# faros-328P-nrf8001-50x70.net
KiCad netlist of a schematic drawn in EAGLE
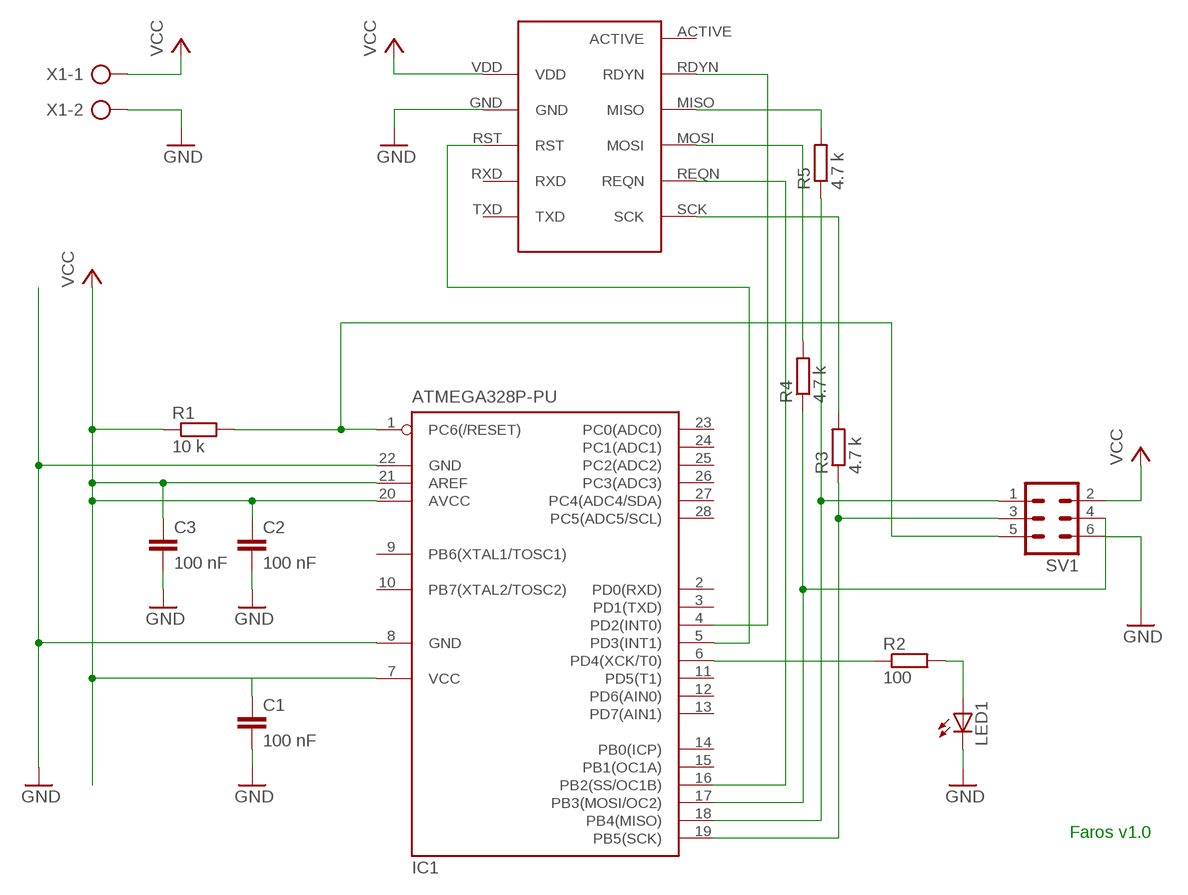
[diagram p0: schematic, sheet 1]

(export (version "E")
  (design (tool "Eeschema 10.0.6"))
  (components
    (comp (ref "C1")
      (value "100 nF")
      (footprint "eagle-import:C050-024X044")
      (libsource (lib "eagle-import") (part "C-EU050-024X044"))
    )
    (comp (ref "C2")
      (value "100 nF")
      (footprint "eagle-import:C050-024X044")
      (libsource (lib "eagle-import") (part "C-EU050-024X044"))
    )
    (comp (ref "C3")
      (value "100 nF")
      (footprint "eagle-import:C050-024X044")
      (libsource (lib "eagle-import") (part "C-EU050-024X044"))
    )
    (comp (ref "IC1")
      (value "ATMEGA328P-PU")
      (footprint "eagle-import:DIL28-3")
      (libsource (lib "eagle-import") (part "MEGA8-P"))
    )
    (comp (ref "LED1")
      (value "LED3MM")
      (footprint "eagle-import:LED3MM")
      (libsource (lib "eagle-import") (part "LED3MM"))
    )
    (comp (ref "MOD1")
      (value "MOD-NRF8001MOD-NRF8001")
      (footprint "eagle-import:MOD-NRF8001")
      (libsource (lib "eagle-import") (part "MOD-NRF8001MOD-NRF8001"))
    )
    (comp (ref "R1")
      (value "10 k")
      (footprint "eagle-import:0207_7")
      (libsource (lib "eagle-import") (part "R-EU_0207/7"))
    )
    (comp (ref "R2")
      (value "100")
      (footprint "eagle-import:0207_7")
      (libsource (lib "eagle-import") (part "R-EU_0207/7"))
    )
    (comp (ref "R3")
      (value "4.7 k")
      (footprint "eagle-import:0207_7")
      (libsource (lib "eagle-import") (part "R-EU_0207/7"))
    )
    (comp (ref "R4")
      (value "4.7 k")
      (footprint "eagle-import:0207_7")
      (libsource (lib "eagle-import") (part "R-EU_0207/7"))
    )
    (comp (ref "R5")
      (value "4.7 k")
      (footprint "eagle-import:0207_7")
      (libsource (lib "eagle-import") (part "R-EU_0207/7"))
    )
    (comp (ref "SV1")
      (value "MA03-2")
      (footprint "eagle-import:MA03-2")
      (libsource (lib "eagle-import") (part "MA03-2"))
    )
    (comp (ref "X1")
      (value "AK500/2")
      (footprint "eagle-import:AK500_2")
      (libsource (lib "eagle-import") (part "AK500/2"))
    )
  )
  (nets
    (net (code "1") (name "GND") (class "Default")
      (node (ref "C1") (pin "2") (pinfunction "2_2") (pintype "passive"))
      (node (ref "C2") (pin "2") (pinfunction "2_2") (pintype "passive"))
      (node (ref "C3") (pin "2") (pinfunction "2_2") (pintype "passive"))
      (node (ref "IC1") (pin "22") (pinfunction "GND_22") (pintype "power_in"))
      (node (ref "IC1") (pin "8") (pinfunction "GND_8") (pintype "power_in"))
      (node (ref "LED1") (pin "K") (pinfunction "C_K") (pintype "passive"))
      (node (ref "MOD1") (pin "GND") (pinfunction "GND_GND") (pintype "power_in"))
      (node (ref "SV1") (pin "6") (pinfunction "6_6") (pintype "passive"))
      (node (ref "X1") (pin "2") (pinfunction "KL_2") (pintype "passive"))
    )
    (net (code "2") (name "Net-(IC1-PB2(SS{slash}OC1B))") (class "Default")
      (node (ref "IC1") (pin "16") (pinfunction "PB2(SS/OC1B)_16") (pintype "bidirectional"))
      (node (ref "MOD1") (pin "REQN") (pinfunction "REQN_REQN") (pintype "input"))
    )
    (net (code "3") (name "Net-(IC1-PB3(MOSI{slash}OC2))") (class "Default")
      (node (ref "IC1") (pin "17") (pinfunction "PB3(MOSI/OC2)_17") (pintype "bidirectional"))
      (node (ref "R4") (pin "1") (pinfunction "1_1") (pintype "passive"))
      (node (ref "SV1") (pin "4") (pinfunction "4_4") (pintype "passive"))
    )
    (net (code "4") (name "Net-(IC1-PB4(MISO))") (class "Default")
      (node (ref "IC1") (pin "18") (pinfunction "PB4(MISO)_18") (pintype "bidirectional"))
      (node (ref "R5") (pin "1") (pinfunction "1_1") (pintype "passive"))
      (node (ref "SV1") (pin "1") (pinfunction "1_1") (pintype "passive"))
    )
    (net (code "5") (name "Net-(IC1-PB5(SCK))") (class "Default")
      (node (ref "IC1") (pin "19") (pinfunction "PB5(SCK)_19") (pintype "bidirectional"))
      (node (ref "R3") (pin "1") (pinfunction "1_1") (pintype "passive"))
      (node (ref "SV1") (pin "3") (pinfunction "3_3") (pintype "passive"))
    )
    (net (code "6") (name "Net-(IC1-PC6({slash}RESET))") (class "Default")
      (node (ref "IC1") (pin "1") (pinfunction "PC6(/RESET)_1") (pintype "bidirectional"))
      (node (ref "R1") (pin "2") (pinfunction "2_2") (pintype "passive"))
      (node (ref "SV1") (pin "5") (pinfunction "5_5") (pintype "passive"))
    )
    (net (code "7") (name "Net-(IC1-PD2(INT0))") (class "Default")
      (node (ref "IC1") (pin "4") (pinfunction "PD2(INT0)_4") (pintype "bidirectional"))
      (node (ref "MOD1") (pin "RDYN") (pinfunction "RDYN_RDYN") (pintype "output"))
    )
    (net (code "8") (name "Net-(IC1-PD3(INT1))") (class "Default")
      (node (ref "IC1") (pin "5") (pinfunction "PD3(INT1)_5") (pintype "bidirectional"))
      (node (ref "MOD1") (pin "RST") (pinfunction "RST_RST") (pintype "input"))
    )
    (net (code "9") (name "Net-(IC1-PD4(XCK{slash}T0))") (class "Default")
      (node (ref "IC1") (pin "6") (pinfunction "PD4(XCK/T0)_6") (pintype "bidirectional"))
      (node (ref "R2") (pin "1") (pinfunction "1_1") (pintype "passive"))
    )
    (net (code "10") (name "Net-(LED1-PadA)") (class "Default")
      (node (ref "LED1") (pin "A") (pinfunction "A_A") (pintype "passive"))
      (node (ref "R2") (pin "2") (pinfunction "2_2") (pintype "passive"))
    )
    (net (code "11") (name "Net-(MOD1-PadMISO)") (class "Default")
      (node (ref "MOD1") (pin "MISO") (pinfunction "MISO_MISO") (pintype "output"))
      (node (ref "R5") (pin "2") (pinfunction "2_2") (pintype "passive"))
    )
    (net (code "12") (name "Net-(MOD1-PadMOSI)") (class "Default")
      (node (ref "MOD1") (pin "MOSI") (pinfunction "MOSI_MOSI") (pintype "input"))
      (node (ref "R4") (pin "2") (pinfunction "2_2") (pintype "passive"))
    )
    (net (code "13") (name "Net-(MOD1-PadSCK)") (class "Default")
      (node (ref "MOD1") (pin "SCK") (pinfunction "SCK_SCK") (pintype "input"))
      (node (ref "R3") (pin "2") (pinfunction "2_2") (pintype "passive"))
    )
    (net (code "14") (name "VCC") (class "Default")
      (node (ref "C1") (pin "1") (pinfunction "1_1") (pintype "passive"))
      (node (ref "C2") (pin "1") (pinfunction "1_1") (pintype "passive"))
      (node (ref "C3") (pin "1") (pinfunction "1_1") (pintype "passive"))
      (node (ref "IC1") (pin "20") (pinfunction "AVCC_20") (pintype "power_in"))
      (node (ref "IC1") (pin "21") (pinfunction "AREF_21") (pintype "passive"))
      (node (ref "IC1") (pin "7") (pinfunction "VCC_7") (pintype "power_in"))
      (node (ref "MOD1") (pin "VDD") (pinfunction "VDD_VDD") (pintype "power_in"))
      (node (ref "R1") (pin "1") (pinfunction "1_1") (pintype "passive"))
      (node (ref "SV1") (pin "2") (pinfunction "2_2") (pintype "passive"))
      (node (ref "X1") (pin "1") (pinfunction "KL_1") (pintype "passive"))
    )
    (net (code "15") (name "unconnected-(IC1-PB0(ICP)-Pad14)") (class "Default")
      (node (ref "IC1") (pin "14") (pinfunction "PB0(ICP)_14") (pintype "bidirectional"))
    )
    (net (code "16") (name "unconnected-(IC1-PB1(OC1A)-Pad15)") (class "Default")
      (node (ref "IC1") (pin "15") (pinfunction "PB1(OC1A)_15") (pintype "bidirectional"))
    )
    (net (code "17") (name "unconnected-(IC1-PB6(XTAL1{slash}TOSC1)-Pad9)") (class "Default")
      (node (ref "IC1") (pin "9") (pinfunction "PB6(XTAL1/TOSC1)_9") (pintype "bidirectional"))
    )
    (net (code "18") (name "unconnected-(IC1-PB7(XTAL2{slash}TOSC2)-Pad10)") (class "Default")
      (node (ref "IC1") (pin "10") (pinfunction "PB7(XTAL2/TOSC2)_10") (pintype "bidirectional"))
    )
    (net (code "19") (name "unconnected-(IC1-PC0(ADC0)-Pad23)") (class "Default")
      (node (ref "IC1") (pin "23") (pinfunction "PC0(ADC0)_23") (pintype "bidirectional"))
    )
    (net (code "20") (name "unconnected-(IC1-PC1(ADC1)-Pad24)") (class "Default")
      (node (ref "IC1") (pin "24") (pinfunction "PC1(ADC1)_24") (pintype "bidirectional"))
    )
    (net (code "21") (name "unconnected-(IC1-PC2(ADC2)-Pad25)") (class "Default")
      (node (ref "IC1") (pin "25") (pinfunction "PC2(ADC2)_25") (pintype "bidirectional"))
    )
    (net (code "22") (name "unconnected-(IC1-PC3(ADC3)-Pad26)") (class "Default")
      (node (ref "IC1") (pin "26") (pinfunction "PC3(ADC3)_26") (pintype "bidirectional"))
    )
    (net (code "23") (name "unconnected-(IC1-PC4(ADC4{slash}SDA)-Pad27)") (class "Default")
      (node (ref "IC1") (pin "27") (pinfunction "PC4(ADC4/SDA)_27") (pintype "bidirectional"))
    )
    (net (code "24") (name "unconnected-(IC1-PC5(ADC5{slash}SCL)-Pad28)") (class "Default")
      (node (ref "IC1") (pin "28") (pinfunction "PC5(ADC5/SCL)_28") (pintype "bidirectional"))
    )
    (net (code "25") (name "unconnected-(IC1-PD0(RXD)-Pad2)") (class "Default")
      (node (ref "IC1") (pin "2") (pinfunction "PD0(RXD)_2") (pintype "bidirectional"))
    )
    (net (code "26") (name "unconnected-(IC1-PD1(TXD)-Pad3)") (class "Default")
      (node (ref "IC1") (pin "3") (pinfunction "PD1(TXD)_3") (pintype "bidirectional"))
    )
    (net (code "27") (name "unconnected-(IC1-PD5(T1)-Pad11)") (class "Default")
      (node (ref "IC1") (pin "11") (pinfunction "PD5(T1)_11") (pintype "bidirectional"))
    )
    (net (code "28") (name "unconnected-(IC1-PD6(AIN0)-Pad12)") (class "Default")
      (node (ref "IC1") (pin "12") (pinfunction "PD6(AIN0)_12") (pintype "bidirectional"))
    )
    (net (code "29") (name "unconnected-(IC1-PD7(AIN1)-Pad13)") (class "Default")
      (node (ref "IC1") (pin "13") (pinfunction "PD7(AIN1)_13") (pintype "bidirectional"))
    )
    (net (code "30") (name "unconnected-(MOD1-PadACTIVE)") (class "Default")
      (node (ref "MOD1") (pin "ACTIVE") (pinfunction "ACTIVE_ACTIVE") (pintype "output"))
    )
    (net (code "31") (name "unconnected-(MOD1-PadRXD)") (class "Default")
      (node (ref "MOD1") (pin "RXD") (pinfunction "RXD_RXD") (pintype "input"))
    )
    (net (code "32") (name "unconnected-(MOD1-PadTXD)") (class "Default")
      (node (ref "MOD1") (pin "TXD") (pinfunction "TXD_TXD") (pintype "output"))
    )
  )
)
